# BlinkerAA.net
KiCad netlist of a schematic drawn in EAGLE
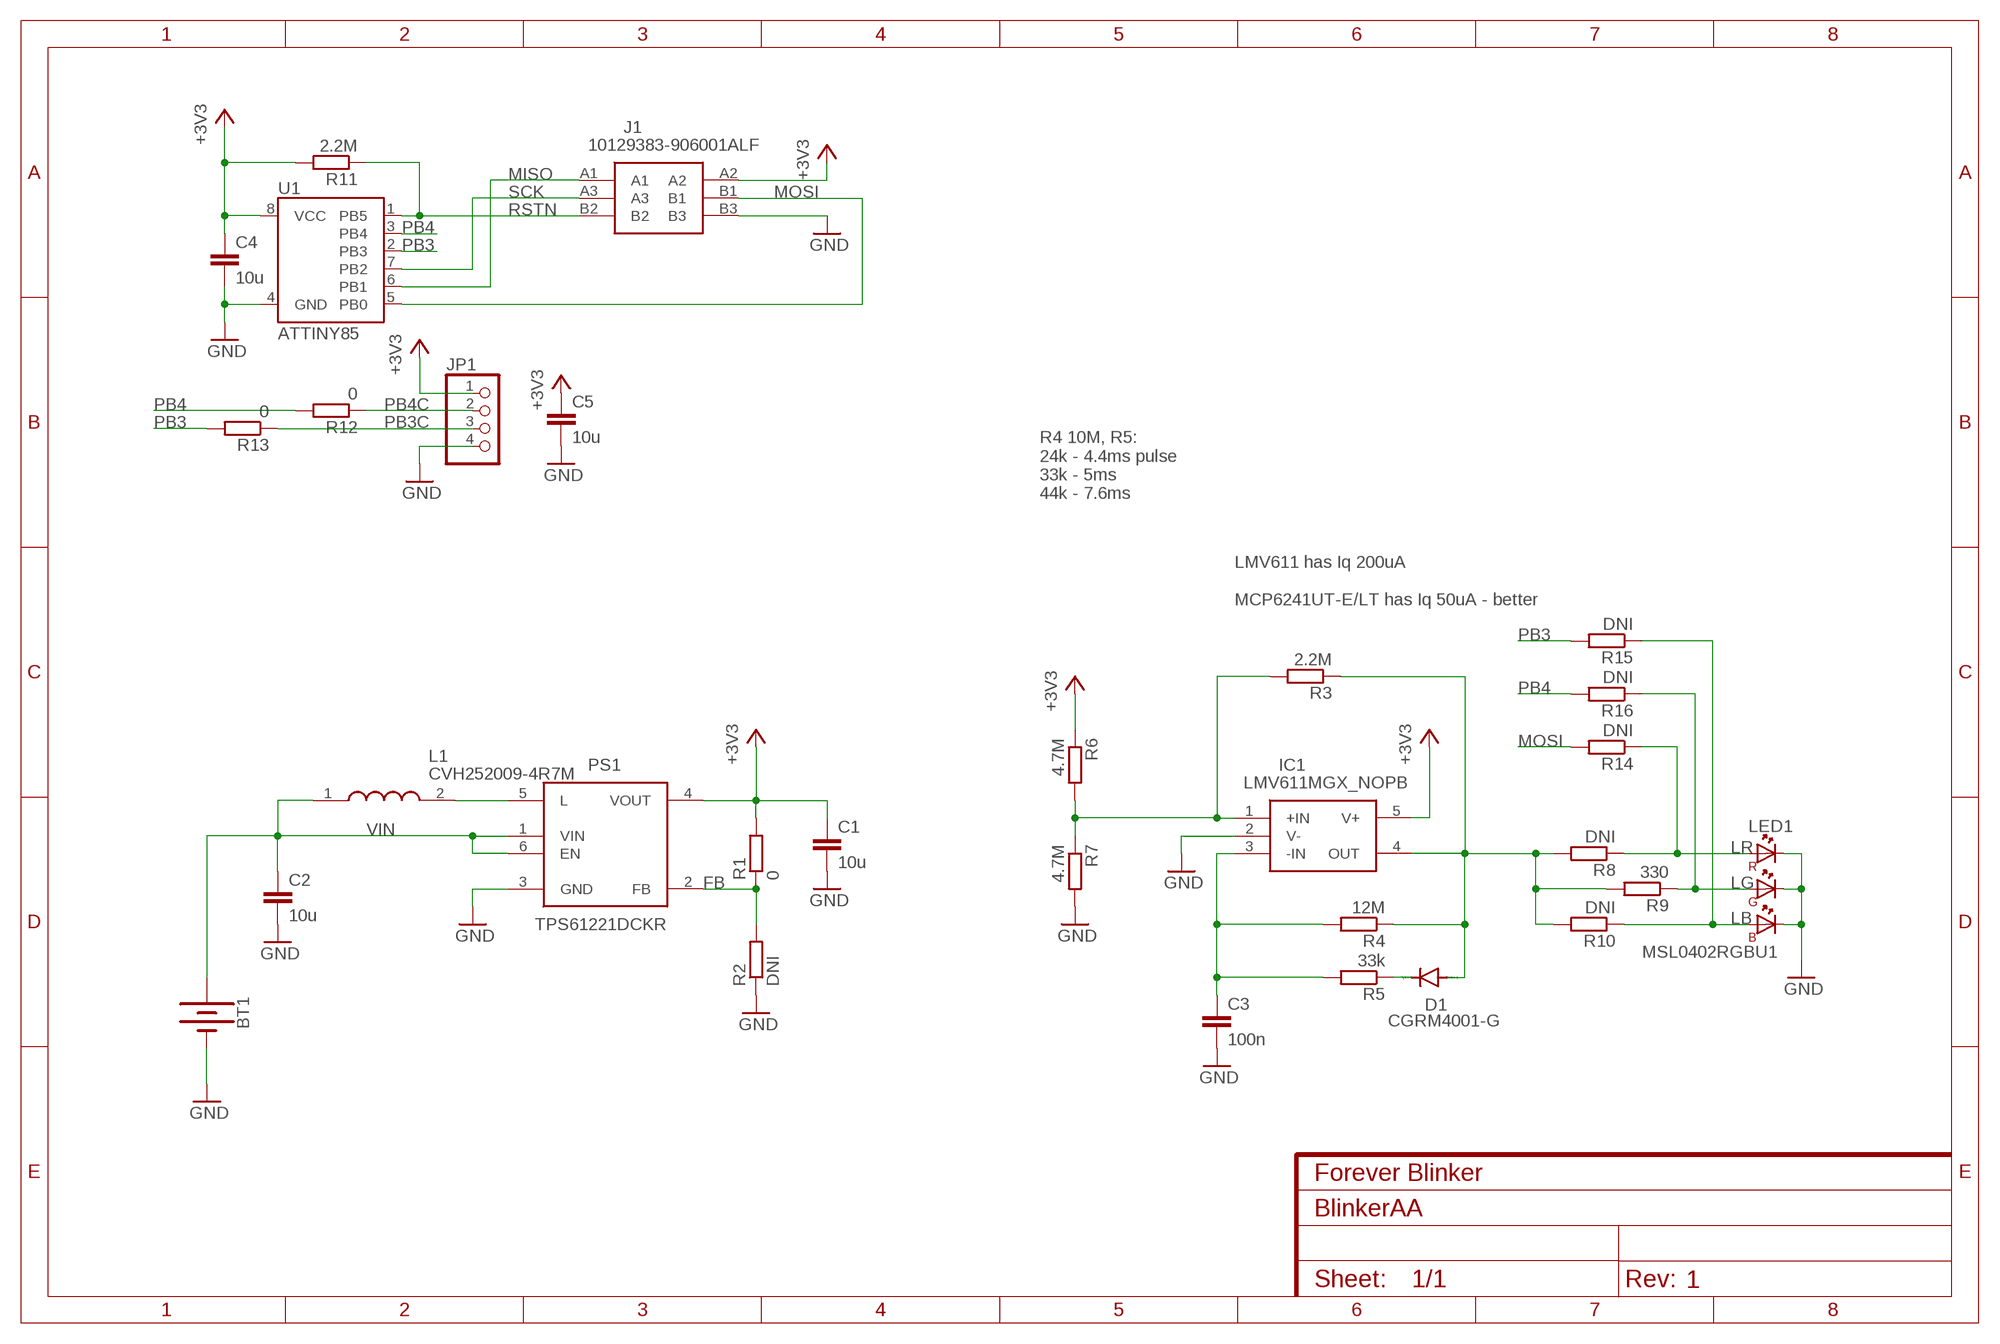
[diagram p0: schematic, sheet 1]

(export (version "E")
  (design (tool "Eeschema 10.0.6"))
  (components
    (comp (ref "BT1")
      (value "BATTERY-AA")
      (footprint "eagle-import:BATTERY-AA")
      (libsource (lib "eagle-import") (part "BATTERY-AA"))
    )
    (comp (ref "C1")
      (value "10u")
      (footprint "eagle-import:C0603K")
      (fields (field (name "PARTNO") "GRM188R61A106KE69J"))
      (libsource (lib "eagle-import") (part "C-EUC0603K"))
    )
    (comp (ref "C2")
      (value "10u")
      (footprint "eagle-import:C0603K")
      (fields (field (name "PARTNO") "GRM188R61A106KE69J"))
      (libsource (lib "eagle-import") (part "C-EUC0603K"))
    )
    (comp (ref "C3")
      (value "100n")
      (footprint "eagle-import:C0603K")
      (fields (field (name "PARTNO") "GRM188R61A106KE69J"))
      (libsource (lib "eagle-import") (part "C-EUC0603K"))
    )
    (comp (ref "C4")
      (value "10u")
      (footprint "eagle-import:C0603K")
      (fields (field (name "PARTNO") "GRM188R61A106KE69J"))
      (libsource (lib "eagle-import") (part "C-EUC0603K"))
    )
    (comp (ref "C5")
      (value "10u")
      (footprint "eagle-import:C0603K")
      (fields (field (name "PARTNO") "GRM188R61A106KE69J"))
      (libsource (lib "eagle-import") (part "C-EUC0603K"))
    )
    (comp (ref "D1")
      (value "CGRM4001-G")
      (footprint "eagle-import:SOD-123_MINI-SMA")
      (libsource (lib "eagle-import") (part "CGRM400-G1"))
    )
    (comp (ref "IC1")
      (value "LMV611MGX_NOPB")
      (footprint "eagle-import:SOT65P210X110-5N")
      (fields (field (name "MANUFACTURER_PART_NUMBER") "LMV611MGX/NOPB"))
      (libsource (lib "eagle-import") (part "LMV611MGX_NOPB"))
    )
    (comp (ref "J1")
      (value "10129383-906001ALF")
      (footprint "eagle-import:10129383906001ALF")
      (fields (field (name "MOUSER_PART_NUMBER") "649-1012938390601ALF"))
      (libsource (lib "eagle-import") (part "10129383-906001ALF"))
    )
    (comp (ref "JP1")
      (value "PINHD-1X4")
      (footprint "eagle-import:1X04")
      (libsource (lib "eagle-import") (part "PINHD-1X4"))
    )
    (comp (ref "L1")
      (value "CVH252009-4R7M")
      (footprint "eagle-import:INDC2520X100N")
      (fields (field (name "MOUSER_PART_NUMBER") "652-CVH252009-4R7M"))
      (libsource (lib "eagle-import") (part "CVH252009-4R7M"))
    )
    (comp (ref "LED1")
      (value "MSL0402RGBU1")
      (footprint "eagle-import:MSL0402RGBU1")
      (fields (field (name "MOUSER_PART_NUMBER") "755-MSL0402RGBU1"))
      (libsource (lib "eagle-import") (part "MSL0402RGBU1"))
    )
    (comp (ref "PS1")
      (value "TPS61221DCKR")
      (footprint "eagle-import:SOT65P210X110-6N")
      (libsource (lib "eagle-import") (part "TPS61221DCKR"))
    )
    (comp (ref "R1")
      (value "0")
      (footprint "eagle-import:R0603")
      (libsource (lib "eagle-import") (part "R-EU_R0603"))
    )
    (comp (ref "R2")
      (value "DNI")
      (footprint "eagle-import:R0603")
      (libsource (lib "eagle-import") (part "R-EU_R0603"))
    )
    (comp (ref "R3")
      (value "2.2M")
      (footprint "eagle-import:R0603")
      (libsource (lib "eagle-import") (part "R-EU_R0603"))
    )
    (comp (ref "R4")
      (value "12M")
      (footprint "eagle-import:R0603")
      (libsource (lib "eagle-import") (part "R-EU_R0603"))
    )
    (comp (ref "R5")
      (value "33k")
      (footprint "eagle-import:R0603")
      (libsource (lib "eagle-import") (part "R-EU_R0603"))
    )
    (comp (ref "R6")
      (value "4.7M")
      (footprint "eagle-import:R0603")
      (libsource (lib "eagle-import") (part "R-EU_R0603"))
    )
    (comp (ref "R7")
      (value "4.7M")
      (footprint "eagle-import:R0603")
      (libsource (lib "eagle-import") (part "R-EU_R0603"))
    )
    (comp (ref "R8")
      (value "DNI")
      (footprint "eagle-import:R0603")
      (libsource (lib "eagle-import") (part "R-EU_R0603"))
    )
    (comp (ref "R9")
      (value "330")
      (footprint "eagle-import:R0603")
      (libsource (lib "eagle-import") (part "R-EU_R0603"))
    )
    (comp (ref "R10")
      (value "DNI")
      (footprint "eagle-import:R0603")
      (libsource (lib "eagle-import") (part "R-EU_R0603"))
    )
    (comp (ref "R11")
      (value "2.2M")
      (footprint "eagle-import:R0603")
      (libsource (lib "eagle-import") (part "R-EU_R0603"))
    )
    (comp (ref "R12")
      (value "0")
      (footprint "eagle-import:R0603")
      (libsource (lib "eagle-import") (part "R-EU_R0603"))
    )
    (comp (ref "R13")
      (value "0")
      (footprint "eagle-import:R0603")
      (libsource (lib "eagle-import") (part "R-EU_R0603"))
    )
    (comp (ref "R14")
      (value "DNI")
      (footprint "eagle-import:R0603")
      (libsource (lib "eagle-import") (part "R-EU_R0603"))
    )
    (comp (ref "R15")
      (value "DNI")
      (footprint "eagle-import:R0603")
      (libsource (lib "eagle-import") (part "R-EU_R0603"))
    )
    (comp (ref "R16")
      (value "DNI")
      (footprint "eagle-import:R0603")
      (libsource (lib "eagle-import") (part "R-EU_R0603"))
    )
    (comp (ref "U1")
      (value "ATTINY85")
      (footprint "eagle-import:ATTINY85")
      (libsource (lib "eagle-import") (part "ATTINY85"))
    )
  )
  (nets
    (net (code "1") (name "+3V3") (class "Default")
      (node (ref "C1") (pin "1") (pinfunction "1_1") (pintype "passive"))
      (node (ref "C4") (pin "1") (pinfunction "1_1") (pintype "passive"))
      (node (ref "C5") (pin "1") (pinfunction "1_1") (pintype "passive"))
      (node (ref "IC1") (pin "5") (pinfunction "V+_5") (pintype "power_in"))
      (node (ref "J1") (pin "A2") (pinfunction "A2_A2") (pintype "bidirectional"))
      (node (ref "JP1") (pin "1") (pinfunction "1_1") (pintype "passive"))
      (node (ref "PS1") (pin "4") (pinfunction "VOUT_4") (pintype "bidirectional"))
      (node (ref "R1") (pin "2") (pinfunction "2_2") (pintype "passive"))
      (node (ref "R11") (pin "2") (pinfunction "2_2") (pintype "passive"))
      (node (ref "R6") (pin "1") (pinfunction "1_1") (pintype "passive"))
      (node (ref "U1") (pin "8") (pinfunction "VCC_8") (pintype "bidirectional"))
    )
    (net (code "2") (name "/FB") (class "Default")
      (node (ref "PS1") (pin "2") (pinfunction "FB_2") (pintype "bidirectional"))
      (node (ref "R1") (pin "1") (pinfunction "1_1") (pintype "passive"))
      (node (ref "R2") (pin "2") (pinfunction "2_2") (pintype "passive"))
    )
    (net (code "3") (name "/LB") (class "Default")
      (node (ref "LED1") (pin "6") (pinfunction "A_B_6") (pintype "passive"))
      (node (ref "R10") (pin "1") (pinfunction "1_1") (pintype "passive"))
      (node (ref "R15") (pin "1") (pinfunction "1_1") (pintype "passive"))
    )
    (net (code "4") (name "/LG") (class "Default")
      (node (ref "LED1") (pin "5") (pinfunction "A_G_5") (pintype "passive"))
      (node (ref "R16") (pin "1") (pinfunction "1_1") (pintype "passive"))
      (node (ref "R9") (pin "1") (pinfunction "1_1") (pintype "passive"))
    )
    (net (code "5") (name "/LR") (class "Default")
      (node (ref "LED1") (pin "4") (pinfunction "A_R_4") (pintype "passive"))
      (node (ref "R14") (pin "1") (pinfunction "1_1") (pintype "passive"))
      (node (ref "R8") (pin "1") (pinfunction "1_1") (pintype "passive"))
    )
    (net (code "6") (name "/MISO") (class "Default")
      (node (ref "J1") (pin "A1") (pinfunction "A1_A1") (pintype "bidirectional"))
      (node (ref "U1") (pin "6") (pinfunction "PB1_6") (pintype "bidirectional"))
    )
    (net (code "7") (name "/MOSI") (class "Default")
      (node (ref "J1") (pin "B1") (pinfunction "B1_B1") (pintype "bidirectional"))
      (node (ref "R14") (pin "2") (pinfunction "2_2") (pintype "passive"))
      (node (ref "U1") (pin "5") (pinfunction "PB0_5") (pintype "bidirectional"))
    )
    (net (code "8") (name "/PB3") (class "Default")
      (node (ref "R13") (pin "2") (pinfunction "2_2") (pintype "passive"))
      (node (ref "R15") (pin "2") (pinfunction "2_2") (pintype "passive"))
      (node (ref "U1") (pin "2") (pinfunction "PB3_2") (pintype "bidirectional"))
    )
    (net (code "9") (name "/PB3C") (class "Default")
      (node (ref "JP1") (pin "3") (pinfunction "3_3") (pintype "passive"))
      (node (ref "R13") (pin "1") (pinfunction "1_1") (pintype "passive"))
    )
    (net (code "10") (name "/PB4") (class "Default")
      (node (ref "R12") (pin "2") (pinfunction "2_2") (pintype "passive"))
      (node (ref "R16") (pin "2") (pinfunction "2_2") (pintype "passive"))
      (node (ref "U1") (pin "3") (pinfunction "PB4_3") (pintype "bidirectional"))
    )
    (net (code "11") (name "/PB4C") (class "Default")
      (node (ref "JP1") (pin "2") (pinfunction "2_2") (pintype "passive"))
      (node (ref "R12") (pin "1") (pinfunction "1_1") (pintype "passive"))
    )
    (net (code "12") (name "/RSTN") (class "Default")
      (node (ref "J1") (pin "B2") (pinfunction "B2_B2") (pintype "bidirectional"))
      (node (ref "R11") (pin "1") (pinfunction "1_1") (pintype "passive"))
      (node (ref "U1") (pin "1") (pinfunction "PB5_1") (pintype "bidirectional"))
    )
    (net (code "13") (name "/SCK") (class "Default")
      (node (ref "J1") (pin "A3") (pinfunction "A3_A3") (pintype "bidirectional"))
      (node (ref "U1") (pin "7") (pinfunction "PB2_7") (pintype "bidirectional"))
    )
    (net (code "14") (name "/VIN") (class "Default")
      (node (ref "BT1") (pin "PWR@1") (pinfunction "+_PWR@1") (pintype "power_in"))
      (node (ref "C2") (pin "1") (pinfunction "1_1") (pintype "passive"))
      (node (ref "L1") (pin "1") (pinfunction "1_1") (pintype "bidirectional"))
      (node (ref "PS1") (pin "1") (pinfunction "VIN_1") (pintype "power_in"))
      (node (ref "PS1") (pin "6") (pinfunction "EN_6") (pintype "input"))
    )
    (net (code "15") (name "GND") (class "Default")
      (node (ref "BT1") (pin "GND@1") (pinfunction "-_GND@1") (pintype "power_in"))
      (node (ref "C1") (pin "2") (pinfunction "2_2") (pintype "passive"))
      (node (ref "C2") (pin "2") (pinfunction "2_2") (pintype "passive"))
      (node (ref "C3") (pin "2") (pinfunction "2_2") (pintype "passive"))
      (node (ref "C4") (pin "2") (pinfunction "2_2") (pintype "passive"))
      (node (ref "C5") (pin "2") (pinfunction "2_2") (pintype "passive"))
      (node (ref "IC1") (pin "2") (pinfunction "V-_2") (pintype "power_in"))
      (node (ref "J1") (pin "B3") (pinfunction "B3_B3") (pintype "bidirectional"))
      (node (ref "JP1") (pin "4") (pinfunction "4_4") (pintype "passive"))
      (node (ref "LED1") (pin "1") (pinfunction "K_B_1") (pintype "passive"))
      (node (ref "LED1") (pin "2") (pinfunction "K_G_2") (pintype "passive"))
      (node (ref "LED1") (pin "3") (pinfunction "K_R_3") (pintype "passive"))
      (node (ref "PS1") (pin "3") (pinfunction "GND_3") (pintype "power_in"))
      (node (ref "R2") (pin "1") (pinfunction "1_1") (pintype "passive"))
      (node (ref "R7") (pin "2") (pinfunction "2_2") (pintype "passive"))
      (node (ref "U1") (pin "4") (pinfunction "GND_4") (pintype "bidirectional"))
    )
    (net (code "16") (name "Net-(D1-PadC)") (class "Default")
      (node (ref "D1") (pin "C") (pinfunction "C_C") (pintype "passive"))
      (node (ref "R5") (pin "1") (pinfunction "1_1") (pintype "passive"))
    )
    (net (code "17") (name "Net-(IC1-+IN)") (class "Default")
      (node (ref "IC1") (pin "1") (pinfunction "+IN_1") (pintype "bidirectional"))
      (node (ref "R3") (pin "2") (pinfunction "2_2") (pintype "passive"))
      (node (ref "R6") (pin "2") (pinfunction "2_2") (pintype "passive"))
      (node (ref "R7") (pin "1") (pinfunction "1_1") (pintype "passive"))
    )
    (net (code "18") (name "Net-(IC1--IN)") (class "Default")
      (node (ref "C3") (pin "1") (pinfunction "1_1") (pintype "passive"))
      (node (ref "IC1") (pin "3") (pinfunction "-IN_3") (pintype "bidirectional"))
      (node (ref "R4") (pin "2") (pinfunction "2_2") (pintype "passive"))
      (node (ref "R5") (pin "2") (pinfunction "2_2") (pintype "passive"))
    )
    (net (code "19") (name "Net-(IC1-OUT)") (class "Default")
      (node (ref "D1") (pin "A") (pinfunction "A_A") (pintype "passive"))
      (node (ref "IC1") (pin "4") (pinfunction "OUT_4") (pintype "bidirectional"))
      (node (ref "R10") (pin "2") (pinfunction "2_2") (pintype "passive"))
      (node (ref "R3") (pin "1") (pinfunction "1_1") (pintype "passive"))
      (node (ref "R4") (pin "1") (pinfunction "1_1") (pintype "passive"))
      (node (ref "R8") (pin "2") (pinfunction "2_2") (pintype "passive"))
      (node (ref "R9") (pin "2") (pinfunction "2_2") (pintype "passive"))
    )
    (net (code "20") (name "Net-(PS1-L)") (class "Default")
      (node (ref "L1") (pin "2") (pinfunction "2_2") (pintype "bidirectional"))
      (node (ref "PS1") (pin "5") (pinfunction "L_5") (pintype "bidirectional"))
    )
  )
)
